# MagSwitchRev1_1.net
KiCad netlist of a schematic drawn in EAGLE
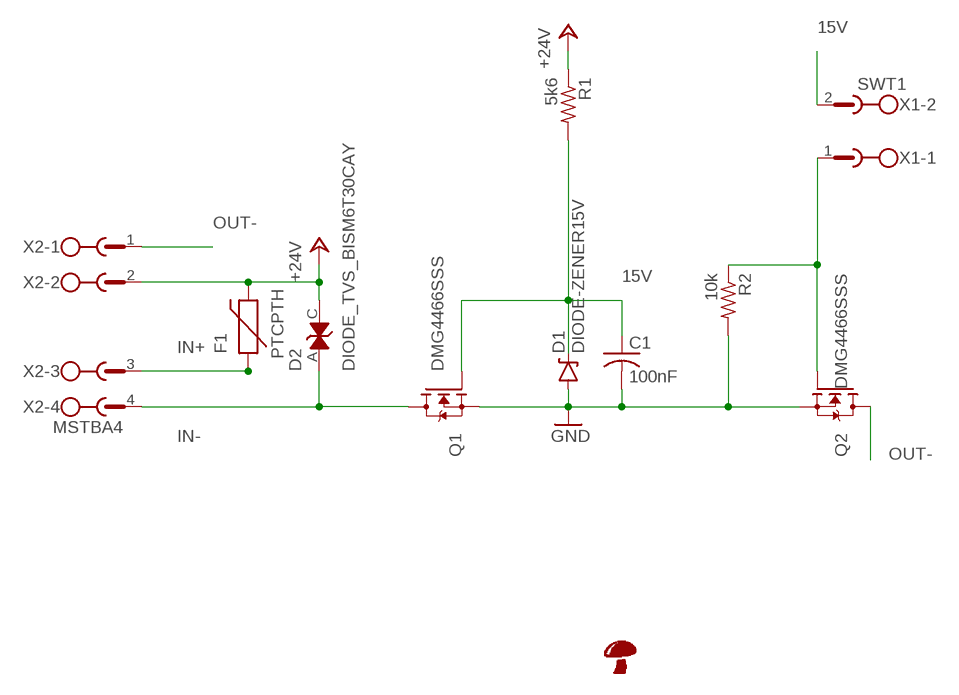
[diagram p0: schematic, sheet 1]

(export (version "E")
  (design (tool "Eeschema 10.0.6"))
  (components
    (comp (ref "C1")
      (value "100nF")
      (footprint "eagle-import:C0805")
      (libsource (lib "eagle-import") (part "C-USC0805"))
    )
    (comp (ref "D1")
      (value "DIODE-ZENER15V")
      (footprint "eagle-import:SOD-323")
      (libsource (lib "eagle-import") (part "DIODE-ZENER15V"))
    )
    (comp (ref "D2")
      (value "DIODE_TVS_BISM6T30CAY")
      (footprint "eagle-import:SMB-DIODE")
      (libsource (lib "eagle-import") (part "DIODE_TVS_BISM6T30CAY"))
    )
    (comp (ref "F1")
      (value "PTCPTH")
      (footprint "eagle-import:PTC")
      (libsource (lib "eagle-import") (part "PTCPTH"))
    )
    (comp (ref "Q1")
      (value "DMG4466SSS")
      (footprint "eagle-import:SO08")
      (libsource (lib "eagle-import") (part "DMG4466SSS"))
    )
    (comp (ref "Q2")
      (value "DMG4466SSS")
      (footprint "eagle-import:SO08")
      (libsource (lib "eagle-import") (part "DMG4466SSS"))
    )
    (comp (ref "R1")
      (value "5k6")
      (footprint "eagle-import:M0805")
      (libsource (lib "eagle-import") (part "R-US_M0805"))
    )
    (comp (ref "R2")
      (value "10k")
      (footprint "eagle-import:M0805")
      (libsource (lib "eagle-import") (part "R-US_M0805"))
    )
    (comp (ref "U$4")
      (value "SHROOM5MM")
      (footprint "eagle-import:SHROOM")
      (libsource (lib "eagle-import") (part "SHROOM5MM"))
    )
    (comp (ref "X1")
      (value "SWT1")
      (footprint "eagle-import:MSTBA2")
      (fields (field (name "MF") "FARNELL") (field (name "MPN") "1757242"))
      (libsource (lib "eagle-import") (part "MSTBA2"))
    )
    (comp (ref "X2")
      (value "MSTBA4")
      (footprint "eagle-import:MSTBA4")
      (fields (field (name "MF") "FARNELL") (field (name "MPN") "1757268"))
      (libsource (lib "eagle-import") (part "MSTBA4"))
    )
  )
  (nets
    (net (code "1") (name "+24V") (class "Default")
      (node (ref "D2") (pin "C") (pinfunction "P$2_C") (pintype "bidirectional"))
      (node (ref "F1") (pin "P$2") (pinfunction "2_P$2") (pintype "bidirectional"))
      (node (ref "R1") (pin "1") (pinfunction "1_1") (pintype "passive"))
      (node (ref "X2") (pin "2") (pinfunction "1_2") (pintype "passive"))
    )
    (net (code "2") (name "/15V") (class "Default")
      (node (ref "C1") (pin "1") (pinfunction "1_1") (pintype "passive"))
      (node (ref "D1") (pin "C") (pinfunction "C_C") (pintype "passive"))
      (node (ref "Q1") (pin "4") (pinfunction "G_4") (pintype "passive"))
      (node (ref "R1") (pin "2") (pinfunction "2_2") (pintype "passive"))
      (node (ref "X1") (pin "2") (pinfunction "1_2") (pintype "passive"))
    )
    (net (code "3") (name "/IN+") (class "Default")
      (node (ref "F1") (pin "P$1") (pinfunction "1_P$1") (pintype "bidirectional"))
      (node (ref "X2") (pin "3") (pinfunction "1_3") (pintype "passive"))
    )
    (net (code "4") (name "/IN-") (class "Default")
      (node (ref "D2") (pin "A") (pinfunction "P$1_A") (pintype "bidirectional"))
      (node (ref "Q1") (pin "5") (pinfunction "D_5") (pintype "passive"))
      (node (ref "Q1") (pin "6") (pinfunction "D_6") (pintype "passive"))
      (node (ref "Q1") (pin "7") (pinfunction "D_7") (pintype "passive"))
      (node (ref "Q1") (pin "8") (pinfunction "D_8") (pintype "passive"))
      (node (ref "X2") (pin "4") (pinfunction "1_4") (pintype "passive"))
    )
    (net (code "5") (name "/OUT-") (class "Default")
      (node (ref "Q2") (pin "5") (pinfunction "D_5") (pintype "passive"))
      (node (ref "Q2") (pin "6") (pinfunction "D_6") (pintype "passive"))
      (node (ref "Q2") (pin "7") (pinfunction "D_7") (pintype "passive"))
      (node (ref "Q2") (pin "8") (pinfunction "D_8") (pintype "passive"))
      (node (ref "X2") (pin "1") (pinfunction "1_1") (pintype "passive"))
    )
    (net (code "6") (name "GND") (class "Default")
      (node (ref "C1") (pin "2") (pinfunction "2_2") (pintype "passive"))
      (node (ref "D1") (pin "A") (pinfunction "A_A") (pintype "passive"))
      (node (ref "Q1") (pin "1") (pinfunction "S_1") (pintype "passive"))
      (node (ref "Q1") (pin "2") (pinfunction "S_2") (pintype "passive"))
      (node (ref "Q1") (pin "3") (pinfunction "S_3") (pintype "passive"))
      (node (ref "Q2") (pin "1") (pinfunction "S_1") (pintype "passive"))
      (node (ref "Q2") (pin "2") (pinfunction "S_2") (pintype "passive"))
      (node (ref "Q2") (pin "3") (pinfunction "S_3") (pintype "passive"))
      (node (ref "R2") (pin "2") (pinfunction "2_2") (pintype "passive"))
    )
    (net (code "7") (name "Net-(Q2-G)") (class "Default")
      (node (ref "Q2") (pin "4") (pinfunction "G_4") (pintype "passive"))
      (node (ref "R2") (pin "1") (pinfunction "1_1") (pintype "passive"))
      (node (ref "X1") (pin "1") (pinfunction "1_1") (pintype "passive"))
    )
  )
)
